# USB_Wireless_Module.net
KiCad netlist of a schematic drawn in Altium Designer
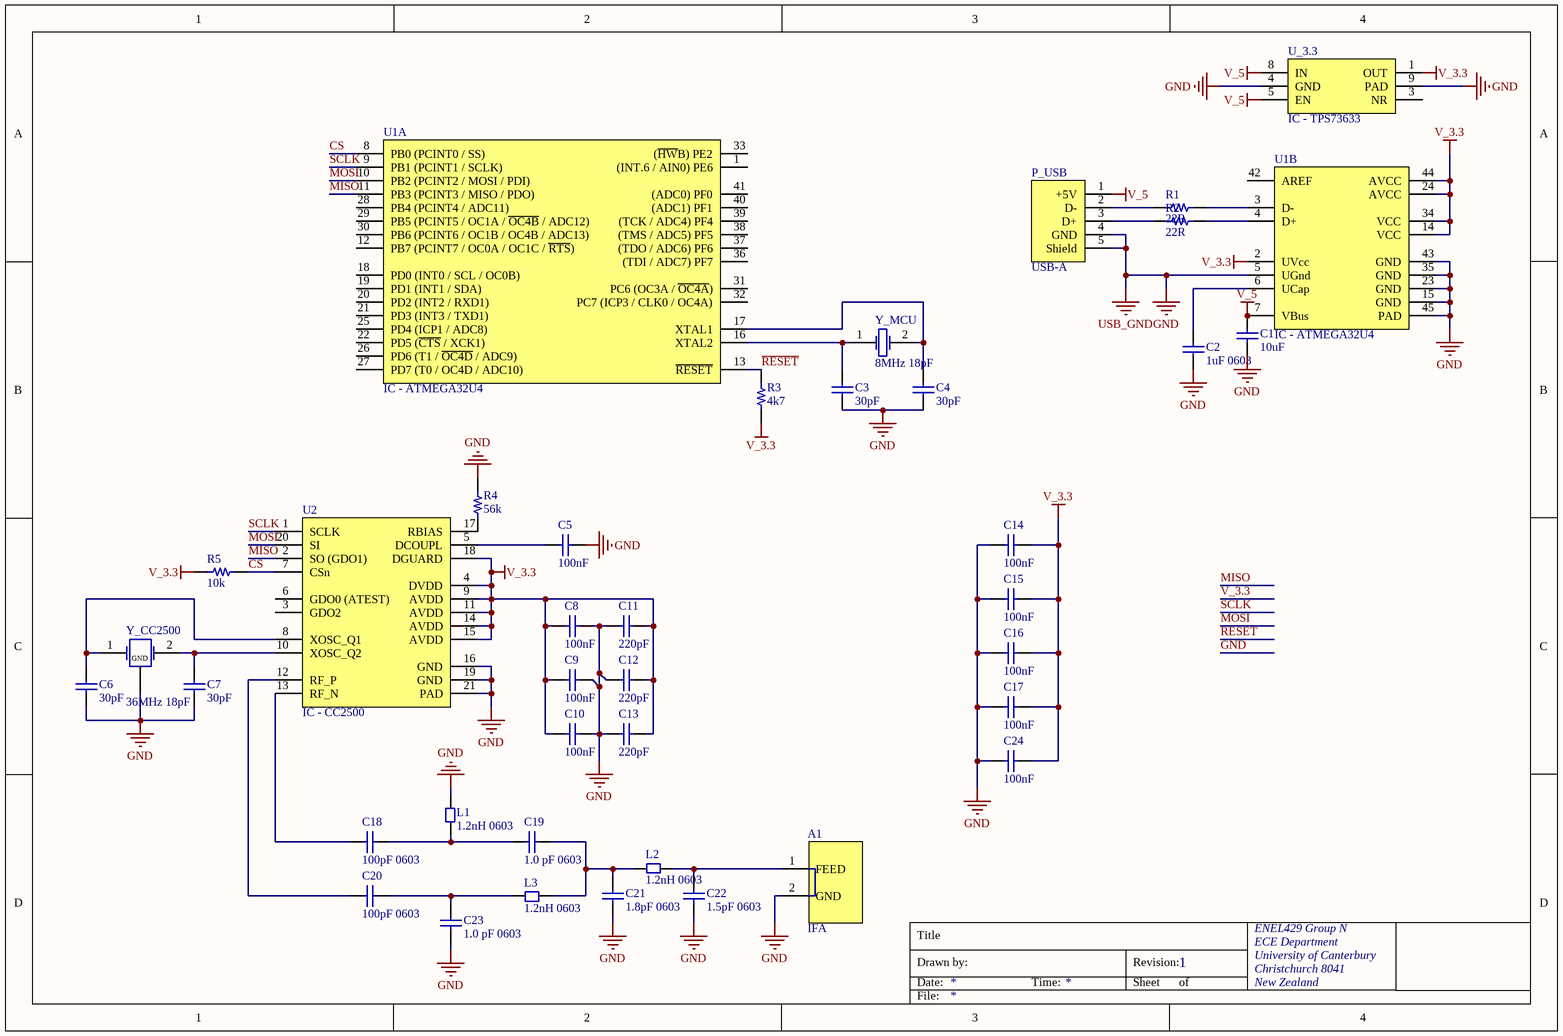
[diagram p0: USB_Wireless_Module.SchDoc]

(export (version "E")
  (design (tool "Eeschema 10.0.6"))
  (components
    (comp (ref "A1")
      (value "IFA")
      (footprint "Meandered_Inverted_F_Antenna")
      (libsource (lib "My Schematic Library") (part "Meandered_Inverted_F_Antenna"))
    )
    (comp (ref "C1")
      (value "10uF")
      (footprint "0603")
      (description "CAP CER 10000PF 50V X7R 0603")
      (fields
        (field (name "MANUFACTURER") "TDK Corporation")
        (field (name "MANUFACTURER PART NUMBER") "C1608X7R1H103M")
      )
      (libsource (lib "My Schematic Library") (part "CP - 10uF 0603"))
    )
    (comp (ref "C2")
      (value "1uF 0603")
      (footprint "0603")
      (description "CAP CER 1.0UF 50V X5S 0603")
      (fields
        (field (name "MANUFACTURER") "Taiyo Yuden")
        (field (name "MANUFACTURER PART NUMBER") "UMK107C5105KA-T")
      )
      (libsource (lib "My Schematic Library") (part "CP - 1uF 0603"))
    )
    (comp (ref "C3")
      (value "30pF")
      (footprint "0603")
      (description "CAP CER 30PF 50V C0G 0603")
      (fields
        (field (name "MANUFACTURER") "TDK Corporation")
        (field (name "MANUFACTURER PART NUMBER") "C1608C0G1H300J")
      )
      (libsource (lib "My Schematic Library") (part "CP - 30pF 0603"))
    )
    (comp (ref "C4")
      (value "30pF")
      (footprint "0603")
      (description "CAP CER 30PF 50V C0G 0603")
      (fields
        (field (name "MANUFACTURER") "TDK Corporation")
        (field (name "MANUFACTURER PART NUMBER") "C1608C0G1H300J")
      )
      (libsource (lib "My Schematic Library") (part "CP - 30pF 0603"))
    )
    (comp (ref "C5")
      (value "100nF")
      (footprint "0603")
      (description "CAP CER .10UF 50V X5R 0603")
      (fields
        (field (name "MANUFACTURER") "AVX Corporation")
        (field (name "MANUFACTURER PART NUMBER") "06035D104KAT2A")
      )
      (libsource (lib "My Schematic Library") (part "CP - 100nF 0603"))
    )
    (comp (ref "C6")
      (value "30pF")
      (footprint "0603")
      (description "CAP CER 30PF 50V C0G 0603")
      (fields
        (field (name "MANUFACTURER") "TDK Corporation")
        (field (name "MANUFACTURER PART NUMBER") "C1608C0G1H300J")
      )
      (libsource (lib "My Schematic Library") (part "CP - 30pF 0603"))
    )
    (comp (ref "C7")
      (value "30pF")
      (footprint "0603")
      (description "CAP CER 30PF 50V C0G 0603")
      (fields
        (field (name "MANUFACTURER") "TDK Corporation")
        (field (name "MANUFACTURER PART NUMBER") "C1608C0G1H300J")
      )
      (libsource (lib "My Schematic Library") (part "CP - 30pF 0603"))
    )
    (comp (ref "C8")
      (value "100nF")
      (footprint "0603")
      (description "CAP CER .10UF 50V X5R 0603")
      (fields
        (field (name "MANUFACTURER") "AVX Corporation")
        (field (name "MANUFACTURER PART NUMBER") "06035D104KAT2A")
      )
      (libsource (lib "My Schematic Library") (part "CP - 100nF 0603"))
    )
    (comp (ref "C9")
      (value "100nF")
      (footprint "0603")
      (description "CAP CER .10UF 50V X5R 0603")
      (fields
        (field (name "MANUFACTURER") "AVX Corporation")
        (field (name "MANUFACTURER PART NUMBER") "06035D104KAT2A")
      )
      (libsource (lib "My Schematic Library") (part "CP - 100nF 0603"))
    )
    (comp (ref "C10")
      (value "100nF")
      (footprint "0603")
      (description "CAP CER .10UF 50V X5R 0603")
      (fields
        (field (name "MANUFACTURER") "AVX Corporation")
        (field (name "MANUFACTURER PART NUMBER") "06035D104KAT2A")
      )
      (libsource (lib "My Schematic Library") (part "CP - 100nF 0603"))
    )
    (comp (ref "C11")
      (value "220pF")
      (footprint "0603")
      (description "CAP CER 220PF 50V NP0 0603")
      (fields
        (field (name "MANUFACTURER") "Johanson Dielectrics Inc")
        (field (name "MANUFACTURER PART NUMBER") "500R14N221JV4T")
      )
      (libsource (lib "My Schematic Library") (part "CP - 220pF 0603"))
    )
    (comp (ref "C12")
      (value "220pF")
      (footprint "0603")
      (description "CAP CER 220PF 50V NP0 0603")
      (fields
        (field (name "MANUFACTURER") "Johanson Dielectrics Inc")
        (field (name "MANUFACTURER PART NUMBER") "500R14N221JV4T")
      )
      (libsource (lib "My Schematic Library") (part "CP - 220pF 0603"))
    )
    (comp (ref "C13")
      (value "220pF")
      (footprint "0603")
      (description "CAP CER 220PF 50V NP0 0603")
      (fields
        (field (name "MANUFACTURER") "Johanson Dielectrics Inc")
        (field (name "MANUFACTURER PART NUMBER") "500R14N221JV4T")
      )
      (libsource (lib "My Schematic Library") (part "CP - 220pF 0603"))
    )
    (comp (ref "C14")
      (value "100nF")
      (footprint "0603")
      (description "CAP CER .10UF 50V X5R 0603")
      (fields
        (field (name "MANUFACTURER") "AVX Corporation")
        (field (name "MANUFACTURER PART NUMBER") "06035D104KAT2A")
      )
      (libsource (lib "My Schematic Library") (part "CP - 100nF 0603"))
    )
    (comp (ref "C15")
      (value "100nF")
      (footprint "0603")
      (description "CAP CER .10UF 50V X5R 0603")
      (fields
        (field (name "MANUFACTURER") "AVX Corporation")
        (field (name "MANUFACTURER PART NUMBER") "06035D104KAT2A")
      )
      (libsource (lib "My Schematic Library") (part "CP - 100nF 0603"))
    )
    (comp (ref "C16")
      (value "100nF")
      (footprint "0603")
      (description "CAP CER .10UF 50V X5R 0603")
      (fields
        (field (name "MANUFACTURER") "AVX Corporation")
        (field (name "MANUFACTURER PART NUMBER") "06035D104KAT2A")
      )
      (libsource (lib "My Schematic Library") (part "CP - 100nF 0603"))
    )
    (comp (ref "C17")
      (value "100nF")
      (footprint "0603")
      (description "CAP CER .10UF 50V X5R 0603")
      (fields
        (field (name "MANUFACTURER") "AVX Corporation")
        (field (name "MANUFACTURER PART NUMBER") "06035D104KAT2A")
      )
      (libsource (lib "My Schematic Library") (part "CP - 100nF 0603"))
    )
    (comp (ref "C18")
      (value "100pF 0603")
      (footprint "0603")
      (description "CAP CERM 100PF 5% 50V NP0 0603")
      (fields
        (field (name "MANUFACTURER") "AVX Corporation")
        (field (name "MANUFACTURER PART NUMBER") "06035A101JAT2A")
      )
      (libsource (lib "My Schematic Library") (part "CP - 100pF 0603"))
    )
    (comp (ref "C19")
      (value "1.0 pF 0603")
      (footprint "0603")
      (description "CAP CER 1.0PF 50V C0G 0603")
      (fields
        (field (name "MANUFACTURER") "TDK Corporation")
        (field (name "MANUFACTURER PART NUMBER") "C1608C0G1H010C")
      )
      (libsource (lib "My Schematic Library") (part "CP - 1.0pF 0603"))
    )
    (comp (ref "C20")
      (value "100pF 0603")
      (footprint "0603")
      (description "CAP CERM 100PF 5% 50V NP0 0603")
      (fields
        (field (name "MANUFACTURER") "AVX Corporation")
        (field (name "MANUFACTURER PART NUMBER") "06035A101JAT2A")
      )
      (libsource (lib "My Schematic Library") (part "CP - 100pF 0603"))
    )
    (comp (ref "C21")
      (value "1.8pF 0603")
      (footprint "0603")
      (description "CAP CER 1.8PF 50V C0G 0603")
      (fields
        (field (name "MANUFACTURER") "TDK Corporation")
        (field (name "MANUFACTURER PART NUMBER") "C1608C0G1H1R8C")
      )
      (libsource (lib "My Schematic Library") (part "CP - 1.8pF 0603"))
    )
    (comp (ref "C22")
      (value "1.5pF 0603")
      (footprint "0603")
      (description "CAP CER 1.5PF 50V C0G 0603")
      (fields
        (field (name "MANUFACTURER") "TDK Corporation")
        (field (name "MANUFACTURER PART NUMBER") "C1608C0G1H1R5C")
      )
      (libsource (lib "My Schematic Library") (part "CP - 1.5pF 0603"))
    )
    (comp (ref "C23")
      (value "1.0 pF 0603")
      (footprint "0603")
      (description "CAP CER 1.0PF 50V C0G 0603")
      (fields
        (field (name "MANUFACTURER") "TDK Corporation")
        (field (name "MANUFACTURER PART NUMBER") "C1608C0G1H010C")
      )
      (libsource (lib "My Schematic Library") (part "CP - 1.0pF 0603"))
    )
    (comp (ref "C24")
      (value "100nF")
      (footprint "0603")
      (description "CAP CER .10UF 50V X5R 0603")
      (fields
        (field (name "MANUFACTURER") "AVX Corporation")
        (field (name "MANUFACTURER PART NUMBER") "06035D104KAT2A")
      )
      (libsource (lib "My Schematic Library") (part "CP - 100nF 0603"))
    )
    (comp (ref "L1")
      (value "1.2nH 0603")
      (footprint "0603")
      (description "INDUCTOR HI FREQ 1.2+/-0.3NH")
      (fields
        (field (name "MANUFACTURER") "Taiyo Yuden")
        (field (name "MANUFACTURER PART NUMBER") "HK16081N2S-T")
      )
      (libsource (lib "My Schematic Library") (part "L - 1.2nH 0603"))
    )
    (comp (ref "L2")
      (value "1.2nH 0603")
      (footprint "0603")
      (description "INDUCTOR HI FREQ 1.2+/-0.3NH")
      (fields
        (field (name "MANUFACTURER") "Taiyo Yuden")
        (field (name "MANUFACTURER PART NUMBER") "HK16081N2S-T")
      )
      (libsource (lib "My Schematic Library") (part "L - 1.2nH 0603"))
    )
    (comp (ref "L3")
      (value "1.2nH 0603")
      (footprint "0603")
      (description "INDUCTOR HI FREQ 1.2+/-0.3NH")
      (fields
        (field (name "MANUFACTURER") "Taiyo Yuden")
        (field (name "MANUFACTURER PART NUMBER") "HK16081N2S-T")
      )
      (libsource (lib "My Schematic Library") (part "L - 1.2nH 0603"))
    )
    (comp (ref "P_USB")
      (value "USB-A")
      (footprint "480372200")
      (description "CONN PLUG USB A 4POS SMD R/A")
      (fields
        (field (name "MANUFACTURER") "Molex Inc")
        (field (name "MANUFACTURER PART NUMBER") "0480372200")
      )
      (libsource (lib "My Schematic Library") (part "H - USB A Plug SMD"))
    )
    (comp (ref "R1")
      (value "22R")
      (footprint "0603")
      (description "RES 22 OHM 1/10W 5% 0603 SMD")
      (fields
        (field (name "MANUFACTURER") "Yageo")
        (field (name "MANUFACTURER PART NUMBER") "RC0603JR-0722RL")
      )
      (libsource (lib "My Schematic Library") (part "RS - 22R 0603"))
    )
    (comp (ref "R2")
      (value "22R")
      (footprint "0603")
      (description "RES 22 OHM 1/10W 5% 0603 SMD")
      (fields
        (field (name "MANUFACTURER") "Yageo")
        (field (name "MANUFACTURER PART NUMBER") "RC0603JR-0722RL")
      )
      (libsource (lib "My Schematic Library") (part "RS - 22R 0603"))
    )
    (comp (ref "R3")
      (value "4k7")
      (footprint "0603")
      (description "RES 4.70K OHM 1/10W 1% 0603 SMD")
      (fields
        (field (name "MANUFACTURER") "Rohm Semiconductor")
        (field (name "MANUFACTURER PART NUMBER") "MCR03EZPFX4701")
      )
      (libsource (lib "My Schematic Library") (part "RS - 4k7 0603"))
    )
    (comp (ref "R4")
      (value "56k")
      (footprint "0603")
      (description "RES 56K OHM 1/10W 5% 0603 SMD")
      (fields
        (field (name "MANUFACTURER") "Yageo")
        (field (name "MANUFACTURER PART NUMBER") "RC0603JR-0756KL")
      )
      (libsource (lib "My Schematic Library") (part "RS - 56k 0603"))
    )
    (comp (ref "R5")
      (value "10k")
      (footprint "0603")
      (description "RES 10.0K OHM 1/10W 1% 0603 SMD")
      (fields
        (field (name "MANUFACTURER") "Yageo")
        (field (name "MANUFACTURER PART NUMBER") "RC0603FR-0710KL")
      )
      (libsource (lib "My Schematic Library") (part "RS - 10k 0603"))
    )
    (comp (ref "U1")
      (value "IC - ATMEGA32U4")
      (footprint "QFN50P700X700X90-44N")
      (description "MCU AVR 32K FLASH 16MHZ 44-QFN")
      (fields (field (name "MANUFACTURER") "Atmel") (field (name "MANUFACTURER PART NUMBER") "ATMEGA32U4-MU"))
      (libsource (lib "My Schematic Library") (part "IC - ATMEGA32U4"))
    )
    (comp (ref "U2")
      (value "IC - CC2500")
      (footprint "TI - RTK / QFN50P400X400X90-20N")
      (description "IC RF TXRX SNGL-CHIP LP 20-QFN")
      (fields
        (field (name "MANUFACTURER") "Texas Instruments")
        (field (name "MANUFACTURER PART NUMBER") "CC2500RTKR")
      )
      (libsource (lib "My Schematic Library") (part "IC - CC2500"))
    )
    (comp (ref "U_3.3")
      (value "IC - TPS73633")
      (footprint "TI - DRB / QFN65P300X300X100-8L")
      (description "IC LDO REG 400MA NO CAP 8-SON")
      (fields
        (field (name "MANUFACTURER") "Texas Instruments")
        (field (name "MANUFACTURER PART NUMBER") "TPS73633DRBR")
      )
      (libsource (lib "My Schematic Library") (part "IC - TPS73633"))
    )
    (comp (ref "Y_CC2500")
      (value "36MHz 18pF")
      (footprint "7M-36.000MAAJ-T")
      (description "CRYSTAL 36.000 MHZ 18PF SMD")
      (fields
        (field (name "MANUFACTURER") "TXC CORPORATION")
        (field (name "MANUFACTURER PART NUMBER") "7M-36.000MAAJ-T")
      )
      (libsource (lib "My Schematic Library") (part "X - 36MHz 18pF"))
    )
    (comp (ref "Y_MCU")
      (value "8MHz 18pF")
      (footprint "ABM7-8.000MHZ-D-2-Y-T")
      (description "CRYSTAL 8.0000 MHZ 18PF SMD")
      (fields
        (field (name "MANUFACTURER") "Abracon Corporation")
        (field (name "MANUFACTURER PART NUMBER") "ABM7-8.000MHZ-D-2-Y-T")
      )
      (libsource (lib "My Schematic Library") (part "X - 8MHz 18pF"))
    )
  )
  (nets
    (net (code "1") (name "/CS") (class "Default")
      (node (ref "R5") (pin "1") (pintype "passive"))
      (node (ref "U1") (pin "8") (pinfunction "PB0_(PCINT0_/_SS)_8") (pintype "passive"))
      (node (ref "U2") (pin "7") (pinfunction "CSn_7") (pintype "passive"))
    )
    (net (code "2") (name "/MISO") (class "Default")
      (node (ref "U1") (pin "11") (pinfunction "PB3_(PCINT3_/_MISO_/_PDO)_11") (pintype "passive"))
      (node (ref "U2") (pin "2") (pinfunction "SO_(GDO1)_2") (pintype "passive"))
    )
    (net (code "3") (name "/MOSI") (class "Default")
      (node (ref "U1") (pin "10") (pinfunction "PB2_(PCINT2_/_MOSI_/_PDI)_10") (pintype "passive"))
      (node (ref "U2") (pin "20") (pinfunction "SI_20") (pintype "passive"))
    )
    (net (code "4") (name "/SCLK") (class "Default")
      (node (ref "U1") (pin "9") (pinfunction "PB1_(PCINT1_/_SCLK)_9") (pintype "passive"))
      (node (ref "U2") (pin "1") (pinfunction "SCLK_1") (pintype "passive"))
    )
    (net (code "5") (name "/~{RESET}") (class "Default")
      (node (ref "R3") (pin "2") (pintype "passive"))
      (node (ref "U1") (pin "13") (pinfunction "~{RESET}_13") (pintype "passive"))
    )
    (net (code "6") (name "GND") (class "Default")
      (node (ref "A1") (pin "2") (pinfunction "GND_2") (pintype "passive"))
      (node (ref "C1") (pin "1") (pintype "passive"))
      (node (ref "C10") (pin "1") (pintype "passive"))
      (node (ref "C11") (pin "1") (pintype "passive"))
      (node (ref "C12") (pin "1") (pintype "passive"))
      (node (ref "C13") (pin "1") (pintype "passive"))
      (node (ref "C14") (pin "2") (pintype "passive"))
      (node (ref "C15") (pin "2") (pintype "passive"))
      (node (ref "C16") (pin "2") (pintype "passive"))
      (node (ref "C17") (pin "2") (pintype "passive"))
      (node (ref "C2") (pin "1") (pintype "passive"))
      (node (ref "C21") (pin "1") (pintype "passive"))
      (node (ref "C22") (pin "1") (pintype "passive"))
      (node (ref "C23") (pin "1") (pintype "passive"))
      (node (ref "C24") (pin "2") (pintype "passive"))
      (node (ref "C3") (pin "1") (pintype "passive"))
      (node (ref "C4") (pin "1") (pintype "passive"))
      (node (ref "C5") (pin "2") (pintype "passive"))
      (node (ref "C6") (pin "1") (pintype "passive"))
      (node (ref "C7") (pin "1") (pintype "passive"))
      (node (ref "C8") (pin "1") (pintype "passive"))
      (node (ref "C9") (pin "1") (pintype "passive"))
      (node (ref "L1") (pin "2") (pintype "passive"))
      (node (ref "P_USB") (pin "4") (pinfunction "GND_4") (pintype "passive"))
      (node (ref "P_USB") (pin "5") (pinfunction "Shield_5") (pintype "passive"))
      (node (ref "R4") (pin "2") (pintype "passive"))
      (node (ref "U1") (pin "15") (pinfunction "GND_15") (pintype "passive"))
      (node (ref "U1") (pin "23") (pinfunction "GND_23") (pintype "passive"))
      (node (ref "U1") (pin "35") (pinfunction "GND_35") (pintype "passive"))
      (node (ref "U1") (pin "43") (pinfunction "GND_43") (pintype "passive"))
      (node (ref "U1") (pin "45") (pinfunction "PAD_45") (pintype "passive"))
      (node (ref "U1") (pin "5") (pinfunction "UGnd_5") (pintype "passive"))
      (node (ref "U2") (pin "16") (pinfunction "GND_16") (pintype "passive"))
      (node (ref "U2") (pin "19") (pinfunction "GND_19") (pintype "passive"))
      (node (ref "U2") (pin "21") (pinfunction "PAD_21") (pintype "passive"))
      (node (ref "U_3.3") (pin "4") (pinfunction "GND_4") (pintype "passive"))
      (node (ref "U_3.3") (pin "9") (pinfunction "PAD_9") (pintype "passive"))
      (node (ref "Y_CC2500") (pin "3") (pinfunction "GND_3") (pintype "passive"))
    )
    (net (code "7") (name "Net-(A1-FEED)") (class "Default")
      (node (ref "A1") (pin "1") (pinfunction "FEED_1") (pintype "passive"))
      (node (ref "C22") (pin "2") (pintype "passive"))
      (node (ref "L2") (pin "2") (pintype "passive"))
    )
    (net (code "8") (name "Net-(C18-Pad2)") (class "Default")
      (node (ref "C18") (pin "2") (pintype "passive"))
      (node (ref "C19") (pin "1") (pintype "passive"))
      (node (ref "L1") (pin "1") (pintype "passive"))
    )
    (net (code "9") (name "Net-(C19-Pad2)") (class "Default")
      (node (ref "C19") (pin "2") (pintype "passive"))
      (node (ref "C21") (pin "2") (pintype "passive"))
      (node (ref "L2") (pin "1") (pintype "passive"))
      (node (ref "L3") (pin "1") (pintype "passive"))
    )
    (net (code "10") (name "Net-(C20-Pad2)") (class "Default")
      (node (ref "C20") (pin "2") (pintype "passive"))
      (node (ref "C23") (pin "2") (pintype "passive"))
      (node (ref "L3") (pin "2") (pintype "passive"))
    )
    (net (code "11") (name "Net-(P_USB-D+)") (class "Default")
      (node (ref "P_USB") (pin "3") (pinfunction "D+_3") (pintype "passive"))
      (node (ref "R2") (pin "1") (pintype "passive"))
    )
    (net (code "12") (name "Net-(P_USB-D-)") (class "Default")
      (node (ref "P_USB") (pin "2") (pinfunction "D-_2") (pintype "passive"))
      (node (ref "R1") (pin "1") (pintype "passive"))
    )
    (net (code "13") (name "Net-(U1A-XTAL1)") (class "Default")
      (node (ref "C4") (pin "2") (pintype "passive"))
      (node (ref "U1") (pin "17") (pinfunction "XTAL1_17") (pintype "passive"))
      (node (ref "Y_MCU") (pin "2") (pintype "passive"))
    )
    (net (code "14") (name "Net-(U1A-XTAL2)") (class "Default")
      (node (ref "C3") (pin "2") (pintype "passive"))
      (node (ref "U1") (pin "16") (pinfunction "XTAL2_16") (pintype "passive"))
      (node (ref "Y_MCU") (pin "1") (pintype "passive"))
    )
    (net (code "15") (name "Net-(U1B-D+)") (class "Default")
      (node (ref "R2") (pin "2") (pintype "passive"))
      (node (ref "U1") (pin "4") (pinfunction "D+_4") (pintype "passive"))
    )
    (net (code "16") (name "Net-(U1B-D-)") (class "Default")
      (node (ref "R1") (pin "2") (pintype "passive"))
      (node (ref "U1") (pin "3") (pinfunction "D-_3") (pintype "passive"))
    )
    (net (code "17") (name "Net-(U1B-UCap)") (class "Default")
      (node (ref "C2") (pin "2") (pintype "passive"))
      (node (ref "U1") (pin "6") (pinfunction "UCap_6") (pintype "passive"))
    )
    (net (code "18") (name "Net-(U2-DCOUPL)") (class "Default")
      (node (ref "C5") (pin "1") (pintype "passive"))
      (node (ref "U2") (pin "5") (pinfunction "DCOUPL_5") (pintype "passive"))
    )
    (net (code "19") (name "Net-(U2-RBIAS)") (class "Default")
      (node (ref "R4") (pin "1") (pintype "passive"))
      (node (ref "U2") (pin "17") (pinfunction "RBIAS_17") (pintype "passive"))
    )
    (net (code "20") (name "Net-(U2-RF_N)") (class "Default")
      (node (ref "C18") (pin "1") (pintype "passive"))
      (node (ref "U2") (pin "13") (pinfunction "RF_N_13") (pintype "passive"))
    )
    (net (code "21") (name "Net-(U2-RF_P)") (class "Default")
      (node (ref "C20") (pin "1") (pintype "passive"))
      (node (ref "U2") (pin "12") (pinfunction "RF_P_12") (pintype "passive"))
    )
    (net (code "22") (name "Net-(U2-XOSC_Q1)") (class "Default")
      (node (ref "C6") (pin "2") (pintype "passive"))
      (node (ref "U2") (pin "8") (pinfunction "XOSC_Q1_8") (pintype "passive"))
      (node (ref "Y_CC2500") (pin "1") (pintype "passive"))
    )
    (net (code "23") (name "Net-(U2-XOSC_Q2)") (class "Default")
      (node (ref "C7") (pin "2") (pintype "passive"))
      (node (ref "U2") (pin "10") (pinfunction "XOSC_Q2_10") (pintype "passive"))
      (node (ref "Y_CC2500") (pin "2") (pintype "passive"))
    )
    (net (code "24") (name "V_3.3") (class "Default")
      (node (ref "C10") (pin "2") (pintype "passive"))
      (node (ref "C11") (pin "2") (pintype "passive"))
      (node (ref "C12") (pin "2") (pintype "passive"))
      (node (ref "C13") (pin "2") (pintype "passive"))
      (node (ref "C14") (pin "1") (pintype "passive"))
      (node (ref "C15") (pin "1") (pintype "passive"))
      (node (ref "C16") (pin "1") (pintype "passive"))
      (node (ref "C17") (pin "1") (pintype "passive"))
      (node (ref "C24") (pin "1") (pintype "passive"))
      (node (ref "C8") (pin "2") (pintype "passive"))
      (node (ref "C9") (pin "2") (pintype "passive"))
      (node (ref "R3") (pin "1") (pintype "passive"))
      (node (ref "R5") (pin "2") (pintype "passive"))
      (node (ref "U1") (pin "14") (pinfunction "VCC_14") (pintype "passive"))
      (node (ref "U1") (pin "2") (pinfunction "UVcc_2") (pintype "passive"))
      (node (ref "U1") (pin "24") (pinfunction "AVCC_24") (pintype "passive"))
      (node (ref "U1") (pin "34") (pinfunction "VCC_34") (pintype "passive"))
      (node (ref "U1") (pin "44") (pinfunction "AVCC_44") (pintype "passive"))
      (node (ref "U2") (pin "11") (pinfunction "AVDD_11") (pintype "passive"))
      (node (ref "U2") (pin "14") (pinfunction "AVDD_14") (pintype "passive"))
      (node (ref "U2") (pin "15") (pinfunction "AVDD_15") (pintype "passive"))
      (node (ref "U2") (pin "18") (pinfunction "DGUARD_18") (pintype "passive"))
      (node (ref "U2") (pin "4") (pinfunction "DVDD_4") (pintype "passive"))
      (node (ref "U2") (pin "9") (pinfunction "AVDD_9") (pintype "passive"))
      (node (ref "U_3.3") (pin "1") (pinfunction "OUT_1") (pintype "passive"))
    )
    (net (code "25") (name "V_5") (class "Default")
      (node (ref "C1") (pin "2") (pintype "passive"))
      (node (ref "P_USB") (pin "1") (pinfunction "+5V_1") (pintype "passive"))
      (node (ref "U1") (pin "7") (pinfunction "VBus_7") (pintype "passive"))
      (node (ref "U_3.3") (pin "5") (pinfunction "EN_5") (pintype "passive"))
      (node (ref "U_3.3") (pin "8") (pinfunction "IN_8") (pintype "passive"))
    )
    (net (code "26") (name "unconnected-(U1A-(ADC0)_PF0-Pad41)") (class "Default")
      (node (ref "U1") (pin "41") (pinfunction "(ADC0)_PF0_41") (pintype "passive"))
    )
    (net (code "27") (name "unconnected-(U1A-(ADC1)_PF1-Pad40)") (class "Default")
      (node (ref "U1") (pin "40") (pinfunction "(ADC1)_PF1_40") (pintype "passive"))
    )
    (net (code "28") (name "unconnected-(U1A-(INT.6_{slash}_AIN0)_PE6-Pad1)") (class "Default")
      (node (ref "U1") (pin "1") (pinfunction "(INT.6_/_AIN0)_PE6_1") (pintype "passive"))
    )
    (net (code "29") (name "unconnected-(U1A-(TCK_{slash}_ADC4)_PF4-Pad39)") (class "Default")
      (node (ref "U1") (pin "39") (pinfunction "(TCK_/_ADC4)_PF4_39") (pintype "passive"))
    )
    (net (code "30") (name "unconnected-(U1A-(TDI_{slash}_ADC7)_PF7-Pad36)") (class "Default")
      (node (ref "U1") (pin "36") (pinfunction "(TDI_/_ADC7)_PF7_36") (pintype "passive"))
    )
    (net (code "31") (name "unconnected-(U1A-(TDO_{slash}_ADC6)_PF6-Pad37)") (class "Default")
      (node (ref "U1") (pin "37") (pinfunction "(TDO_/_ADC6)_PF6_37") (pintype "passive"))
    )
    (net (code "32") (name "unconnected-(U1A-(TMS_{slash}_ADC5)_PF5-Pad38)") (class "Default")
      (node (ref "U1") (pin "38") (pinfunction "(TMS_/_ADC5)_PF5_38") (pintype "passive"))
    )
    (net (code "33") (name "unconnected-(U1A-(~{HW}B)_PE2-Pad33)") (class "Default")
      (node (ref "U1") (pin "33") (pinfunction "(~{HW}B)_PE2_33") (pintype "passive"))
    )
    (net (code "34") (name "unconnected-(U1A-PB4_(PCINT4_{slash}_ADC11)-Pad28)") (class "Default")
      (node (ref "U1") (pin "28") (pinfunction "PB4_(PCINT4_/_ADC11)_28") (pintype "passive"))
    )
    (net (code "35") (name "unconnected-(U1A-PB5_(PCINT5_{slash}_OC1A_{slash}_~{OC4B}_{slash}_ADC12)-Pad29)") (class "Default")
      (node (ref "U1") (pin "29") (pinfunction "PB5_(PCINT5_/_OC1A_/_~{OC4B}_/_ADC12)_29") (pintype "passive"))
    )
    (net (code "36") (name "unconnected-(U1A-PB6_(PCINT6_{slash}_OC1B_{slash}_OC4B_{slash}_ADC13)-Pad30)") (class "Default")
      (node (ref "U1") (pin "30") (pinfunction "PB6_(PCINT6_/_OC1B_/_OC4B_/_ADC13)_30") (pintype "passive"))
    )
    (net (code "37") (name "unconnected-(U1A-PB7_(PCINT7_{slash}_OC0A_{slash}_OC1C_{slash}_~{RTS})-Pad12)") (class "Default")
      (node (ref "U1") (pin "12") (pinfunction "PB7_(PCINT7_/_OC0A_/_OC1C_/_~{RTS})_12") (pintype "passive"))
    )
    (net (code "38") (name "unconnected-(U1A-PC6_(OC3A_{slash}_~{OC4A})-Pad31)") (class "Default")
      (node (ref "U1") (pin "31") (pinfunction "PC6_(OC3A_/_~{OC4A})_31") (pintype "passive"))
    )
    (net (code "39") (name "unconnected-(U1A-PC7_(ICP3_{slash}_CLK0_{slash}_OC4A)-Pad32)") (class "Default")
      (node (ref "U1") (pin "32") (pinfunction "PC7_(ICP3_/_CLK0_/_OC4A)_32") (pintype "passive"))
    )
    (net (code "40") (name "unconnected-(U1A-PD0_(INT0_{slash}_SCL_{slash}_OC0B)-Pad18)") (class "Default")
      (node (ref "U1") (pin "18") (pinfunction "PD0_(INT0_/_SCL_/_OC0B)_18") (pintype "passive"))
    )
    (net (code "41") (name "unconnected-(U1A-PD1_(INT1_{slash}_SDA)-Pad19)") (class "Default")
      (node (ref "U1") (pin "19") (pinfunction "PD1_(INT1_/_SDA)_19") (pintype "passive"))
    )
    (net (code "42") (name "unconnected-(U1A-PD2_(INT2_{slash}_RXD1)-Pad20)") (class "Default")
      (node (ref "U1") (pin "20") (pinfunction "PD2_(INT2_/_RXD1)_20") (pintype "passive"))
    )
    (net (code "43") (name "unconnected-(U1A-PD3_(INT3_{slash}_TXD1)-Pad21)") (class "Default")
      (node (ref "U1") (pin "21") (pinfunction "PD3_(INT3_/_TXD1)_21") (pintype "passive"))
    )
    (net (code "44") (name "unconnected-(U1A-PD4_(ICP1_{slash}_ADC8)-Pad25)") (class "Default")
      (node (ref "U1") (pin "25") (pinfunction "PD4_(ICP1_/_ADC8)_25") (pintype "passive"))
    )
    (net (code "45") (name "unconnected-(U1A-PD5_(~{CTS}_{slash}_XCK1)-Pad22)") (class "Default")
      (node (ref "U1") (pin "22") (pinfunction "PD5_(~{CTS}_/_XCK1)_22") (pintype "passive"))
    )
    (net (code "46") (name "unconnected-(U1A-PD6_(T1_{slash}_~{OC4D}_{slash}_ADC9)-Pad26)") (class "Default")
      (node (ref "U1") (pin "26") (pinfunction "PD6_(T1_/_~{OC4D}_/_ADC9)_26") (pintype "passive"))
    )
    (net (code "47") (name "unconnected-(U1A-PD7_(T0_{slash}_OC4D_{slash}_ADC10)-Pad27)") (class "Default")
      (node (ref "U1") (pin "27") (pinfunction "PD7_(T0_/_OC4D_/_ADC10)_27") (pintype "passive"))
    )
    (net (code "48") (name "unconnected-(U1B-AREF-Pad42)") (class "Default")
      (node (ref "U1") (pin "42") (pinfunction "AREF_42") (pintype "passive"))
    )
    (net (code "49") (name "unconnected-(U2-GDO0_(ATEST)-Pad6)") (class "Default")
      (node (ref "U2") (pin "6") (pinfunction "GDO0_(ATEST)_6") (pintype "passive"))
    )
    (net (code "50") (name "unconnected-(U2-GDO2-Pad3)") (class "Default")
      (node (ref "U2") (pin "3") (pinfunction "GDO2_3") (pintype "passive"))
    )
    (net (code "51") (name "unconnected-(U_3.3-NR-Pad3)") (class "Default")
      (node (ref "U_3.3") (pin "3") (pinfunction "NR_3") (pintype "passive"))
    )
  )
)
